# Actuators.net
KiCad netlist of a schematic drawn in Altium Designer
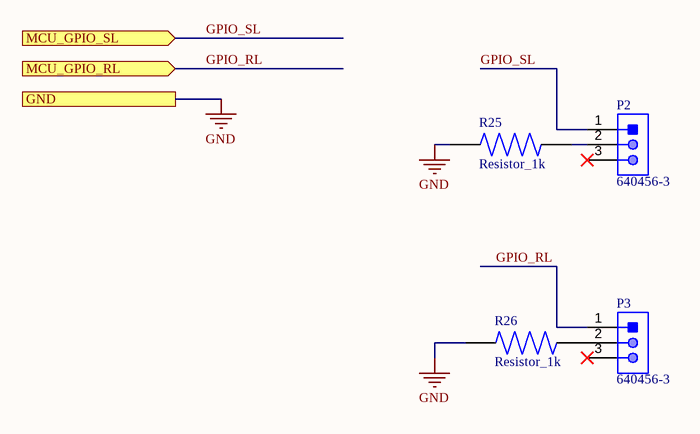
[diagram p0: Actuators.SchDoc]

(export (version "E")
  (design (tool "Eeschema 10.0.6"))
  (components
    (comp (ref "P2")
      (value "640456-3")
      (footprint "TECO-640456-3")
      (description "Male Header, Pitch 2.54 mm, 1 x 3 Position, Height 10.03 mm, Tail Length 3.56 mm, -55 to 105 degC")
      (fields (field (name "MANUFACTURER") "TE Connectivity"))
      (libsource (lib "Altium Content Vault") (part "CN-1P-M-R3"))
    )
    (comp (ref "P3")
      (value "640456-3")
      (footprint "TECO-640456-3")
      (description "Male Header, Pitch 2.54 mm, 1 x 3 Position, Height 10.03 mm, Tail Length 3.56 mm, -55 to 105 degC")
      (fields (field (name "MANUFACTURER") "TE Connectivity"))
      (libsource (lib "Altium Content Vault") (part "CN-1P-M-R3"))
    )
    (comp (ref "R25")
      (value "Resistor_1k")
      (footprint "Resistor_1k")
      (description "Res Thick Film 0603 1K Ohm 1% 0.1W(1/10W) ±100ppm/C Pad SMD Automotive T/R")
      (fields
        (field (name "MANUFACTURER") "TE Connectivity")
        (field (name "MANUFACTURER PART NUMBER") "1-2176092-8")
      )
      (libsource (lib "Schematic_Lib") (part "Resistor_1k"))
    )
    (comp (ref "R26")
      (value "Resistor_1k")
      (footprint "Resistor_1k")
      (description "Res Thick Film 0603 1K Ohm 1% 0.1W(1/10W) ±100ppm/C Pad SMD Automotive T/R")
      (fields
        (field (name "MANUFACTURER") "TE Connectivity")
        (field (name "MANUFACTURER PART NUMBER") "1-2176092-8")
      )
      (libsource (lib "Schematic_Lib") (part "Resistor_1k"))
    )
  )
  (nets
    (net (code "1") (name "/GPIO_RL") (class "Default")
      (node (ref "P3") (pin "1") (pinfunction "1_1") (pintype "passive"))
    )
    (net (code "2") (name "/GPIO_SL") (class "Default")
      (node (ref "P2") (pin "1") (pinfunction "1_1") (pintype "passive"))
    )
    (net (code "3") (name "GND") (class "Default")
      (node (ref "R25") (pin "1") (pinfunction "1_1") (pintype "passive"))
      (node (ref "R26") (pin "1") (pinfunction "1_1") (pintype "passive"))
    )
    (net (code "4") (name "Net-(P2-Pad2)") (class "Default")
      (node (ref "P2") (pin "2") (pinfunction "2_2") (pintype "passive"))
      (node (ref "R25") (pin "2") (pinfunction "2_2") (pintype "passive"))
    )
    (net (code "5") (name "Net-(P3-Pad2)") (class "Default")
      (node (ref "P3") (pin "2") (pinfunction "2_2") (pintype "passive"))
      (node (ref "R26") (pin "2") (pinfunction "2_2") (pintype "passive"))
    )
    (net (code "6") (name "unconnected-(P2-Pad3)") (class "Default")
      (node (ref "P2") (pin "3") (pinfunction "3_3") (pintype "passive+no_connect"))
    )
    (net (code "7") (name "unconnected-(P3-Pad3)") (class "Default")
      (node (ref "P3") (pin "3") (pinfunction "3_3") (pintype "passive+no_connect"))
    )
  )
)
